# Schematic_v27.net
KiCad netlist of a schematic drawn in EAGLE
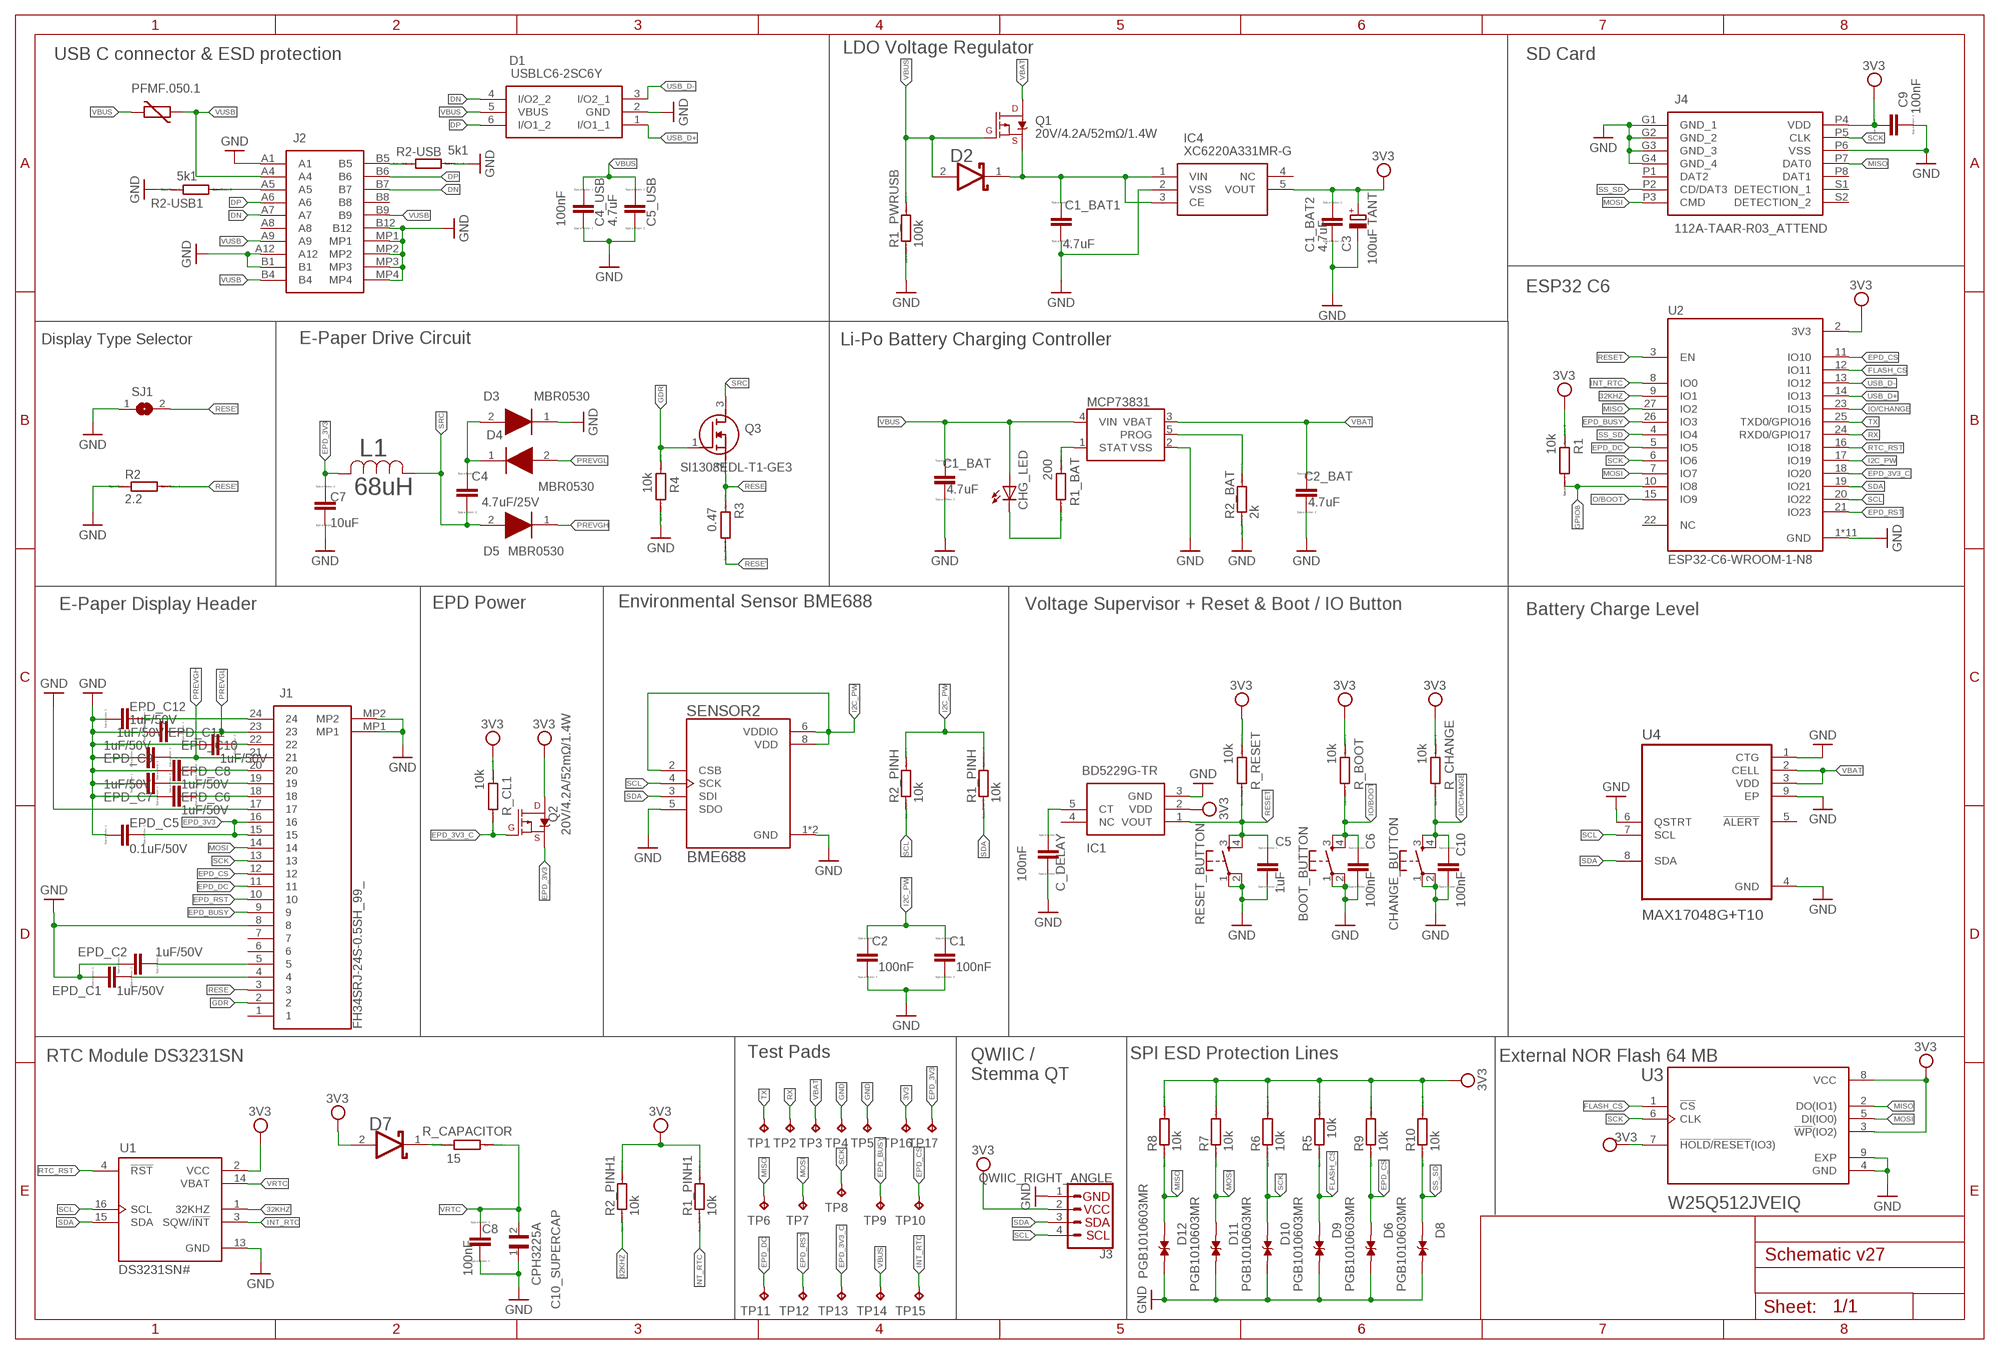
[diagram p0: schematic, sheet 1]

(export (version "E")
  (design (tool "Eeschema 10.0.6"))
  (components
    (comp (ref "BOOT_BUTTON")
      (value "BUTTON_CUSYOMV1")
      (footprint "eagle-import:MYBUTTON")
      (libsource (lib "eagle-import") (part "BUTTON_CUSYOMV1"))
    )
    (comp (ref "C1")
      (value "100nF")
      (footprint "eagle-import:ESP32_WROVER_EAGLE-LTSPICE_C0402")
      (libsource (lib "eagle-import") (part "ESP32_WROVER_EAGLE-LTSPICE_CC0402"))
    )
    (comp (ref "C1_BAT")
      (value "4.7uF")
      (footprint "eagle-import:ESP32_WROVER_EAGLE-LTSPICE_C0402")
      (libsource (lib "eagle-import") (part "ESP32_WROVER_EAGLE-LTSPICE_CC0402"))
    )
    (comp (ref "C1_BAT1")
      (value "4.7uF")
      (footprint "eagle-import:ESP32_WROVER_EAGLE-LTSPICE_C0402")
      (libsource (lib "eagle-import") (part "ESP32_WROVER_EAGLE-LTSPICE_CC0402"))
    )
    (comp (ref "C1_BAT2")
      (value "4.7uF")
      (footprint "eagle-import:ESP32_WROVER_EAGLE-LTSPICE_C0402")
      (libsource (lib "eagle-import") (part "ESP32_WROVER_EAGLE-LTSPICE_CC0402"))
    )
    (comp (ref "C2")
      (value "100nF")
      (footprint "eagle-import:ESP32_WROVER_EAGLE-LTSPICE_C0402")
      (libsource (lib "eagle-import") (part "ESP32_WROVER_EAGLE-LTSPICE_CC0402"))
    )
    (comp (ref "C2_BAT")
      (value "4.7uF")
      (footprint "eagle-import:ESP32_WROVER_EAGLE-LTSPICE_C0402")
      (libsource (lib "eagle-import") (part "ESP32_WROVER_EAGLE-LTSPICE_CC0402"))
    )
    (comp (ref "C3")
      (value "100uF TANT")
      (footprint "eagle-import:RCL_CT3528")
      (libsource (lib "eagle-import") (part "RCL_CPOL-EUCT3528"))
    )
    (comp (ref "C4")
      (value "4.7uF/25V")
      (footprint "eagle-import:ESP32_WROVER_EAGLE-LTSPICE_C0402")
      (libsource (lib "eagle-import") (part "ESP32_WROVER_EAGLE-LTSPICE_CC0402"))
    )
    (comp (ref "C4_USB")
      (value "100nF")
      (footprint "eagle-import:ESP32_WROVER_EAGLE-LTSPICE_C0402")
      (libsource (lib "eagle-import") (part "ESP32_WROVER_EAGLE-LTSPICE_CC0402"))
    )
    (comp (ref "C5")
      (value "1uF")
      (footprint "eagle-import:ESP32_WROVER_EAGLE-LTSPICE_C0402")
      (libsource (lib "eagle-import") (part "ESP32_WROVER_EAGLE-LTSPICE_CC0402"))
    )
    (comp (ref "C5_USB")
      (value "4.7uF")
      (footprint "eagle-import:ESP32_WROVER_EAGLE-LTSPICE_C0402")
      (libsource (lib "eagle-import") (part "ESP32_WROVER_EAGLE-LTSPICE_CC0402"))
    )
    (comp (ref "C6")
      (value "100nF")
      (footprint "eagle-import:ESP32_WROVER_EAGLE-LTSPICE_C0402")
      (libsource (lib "eagle-import") (part "ESP32_WROVER_EAGLE-LTSPICE_CC0402"))
    )
    (comp (ref "C7")
      (value "10uF")
      (footprint "eagle-import:ESP32_WROVER_EAGLE-LTSPICE_C0402")
      (libsource (lib "eagle-import") (part "ESP32_WROVER_EAGLE-LTSPICE_CC0402"))
    )
    (comp (ref "C8")
      (value "100nF")
      (footprint "eagle-import:ESP32_WROVER_EAGLE-LTSPICE_C0402")
      (libsource (lib "eagle-import") (part "ESP32_WROVER_EAGLE-LTSPICE_CC0402"))
    )
    (comp (ref "C9")
      (value "100nF")
      (footprint "eagle-import:ESP32_WROVER_EAGLE-LTSPICE_C0402")
      (libsource (lib "eagle-import") (part "ESP32_WROVER_EAGLE-LTSPICE_CC0402"))
    )
    (comp (ref "C10")
      (value "100nF")
      (footprint "eagle-import:ESP32_WROVER_EAGLE-LTSPICE_C0402")
      (libsource (lib "eagle-import") (part "ESP32_WROVER_EAGLE-LTSPICE_CC0402"))
    )
    (comp (ref "C10_SUPERCAP")
      (value "CPH3225A")
      (footprint "eagle-import:CAPCP3225X100N")
      (fields (field (name "MF") "Seiko Instruments"))
      (libsource (lib "eagle-import") (part "CPH3225A"))
    )
    (comp (ref "CHANGE_BUTTON")
      (value "BUTTON_CUSYOMV1")
      (footprint "eagle-import:MYBUTTON")
      (libsource (lib "eagle-import") (part "BUTTON_CUSYOMV1"))
    )
    (comp (ref "CHG_LED")
      (value "ADAFRUIT_LEDCHIP-LED0603")
      (footprint "eagle-import:ADAFRUIT_CHIP-LED0603")
      (libsource (lib "eagle-import") (part "ADAFRUIT_LEDCHIP-LED0603"))
    )
    (comp (ref "C_DELAY")
      (value "100nF")
      (footprint "eagle-import:ESP32_WROVER_EAGLE-LTSPICE_C0402")
      (libsource (lib "eagle-import") (part "ESP32_WROVER_EAGLE-LTSPICE_CC0402"))
    )
    (comp (ref "D1")
      (value "USBLC6-2SC6Y")
      (footprint "eagle-import:SOT95P280X145-6N")
      (fields (field (name "MF") "STMicroelectronics"))
      (libsource (lib "eagle-import") (part "USBLC6-2SC6Y"))
    )
    (comp (ref "D2")
      (value "ESP32_WROVER_AVX---SD0805S020S1R0_AVX_SD0805S020S1R0_0_0AVX_SD0805S020S1R0_0_0")
      (footprint "eagle-import:ESP32_WROVER_AVX---SD0805S020S1R0_AVX_SD0805S020S1R0_0")
      (fields
        (field (name "DIGIKEY_PART_NUMBER") "478-7800-1-ND")
        (field (name "MF") "AVX")
        (field (name "MOUSER_PART_NUMBER") "581-SD0805S020S1R0")
      )
      (libsource (lib "eagle-import") (part "ESP32_WROVER_AVX---SD0805S020S1R0_AVX_SD0805S020S1R0_0_0AVX_SD0805S020S1R0_0_0"))
    )
    (comp (ref "D3")
      (value "MBR0530")
      (footprint "eagle-import:SOD3716X135N")
      (fields (field (name "MF") "ON Semiconductor"))
      (libsource (lib "eagle-import") (part "MBR0530"))
    )
    (comp (ref "D4")
      (value "MBR0530")
      (footprint "eagle-import:SOD3716X135N")
      (fields (field (name "MF") "ON Semiconductor"))
      (libsource (lib "eagle-import") (part "MBR0530"))
    )
    (comp (ref "D5")
      (value "MBR0530")
      (footprint "eagle-import:SOD3716X135N")
      (fields (field (name "MF") "ON Semiconductor"))
      (libsource (lib "eagle-import") (part "MBR0530"))
    )
    (comp (ref "D6")
      (value "PGB1010603MR")
      (footprint "eagle-import:DIOC1608X36N")
      (fields (field (name "MF") "Littelfuse Inc."))
      (libsource (lib "eagle-import") (part "PGB1010603MR"))
    )
    (comp (ref "D7")
      (value "ESP32_WROVER_AVX---SD0805S020S1R0_AVX_SD0805S020S1R0_0_0AVX_SD0805S020S1R0_0_0")
      (footprint "eagle-import:ESP32_WROVER_AVX---SD0805S020S1R0_AVX_SD0805S020S1R0_0")
      (fields
        (field (name "DIGIKEY_PART_NUMBER") "478-7800-1-ND")
        (field (name "MF") "AVX")
        (field (name "MOUSER_PART_NUMBER") "581-SD0805S020S1R0")
      )
      (libsource (lib "eagle-import") (part "ESP32_WROVER_AVX---SD0805S020S1R0_AVX_SD0805S020S1R0_0_0AVX_SD0805S020S1R0_0_0"))
    )
    (comp (ref "D8")
      (value "PGB1010603MR")
      (footprint "eagle-import:DIOC1608X36N")
      (fields (field (name "MF") "Littelfuse Inc."))
      (libsource (lib "eagle-import") (part "PGB1010603MR"))
    )
    (comp (ref "D9")
      (value "PGB1010603MR")
      (footprint "eagle-import:DIOC1608X36N")
      (fields (field (name "MF") "Littelfuse Inc."))
      (libsource (lib "eagle-import") (part "PGB1010603MR"))
    )
    (comp (ref "D10")
      (value "PGB1010603MR")
      (footprint "eagle-import:DIOC1608X36N")
      (fields (field (name "MF") "Littelfuse Inc."))
      (libsource (lib "eagle-import") (part "PGB1010603MR"))
    )
    (comp (ref "D11")
      (value "PGB1010603MR")
      (footprint "eagle-import:DIOC1608X36N")
      (fields (field (name "MF") "Littelfuse Inc."))
      (libsource (lib "eagle-import") (part "PGB1010603MR"))
    )
    (comp (ref "D12")
      (value "PGB1010603MR")
      (footprint "eagle-import:DIOC1608X36N")
      (fields (field (name "MF") "Littelfuse Inc."))
      (libsource (lib "eagle-import") (part "PGB1010603MR"))
    )
    (comp (ref "EPD_C1")
      (value "1uF/50V")
      (footprint "eagle-import:ESP32_WROVER_EAGLE-LTSPICE_C0402")
      (libsource (lib "eagle-import") (part "ESP32_WROVER_EAGLE-LTSPICE_CC0402"))
    )
    (comp (ref "EPD_C2")
      (value "1uF/50V")
      (footprint "eagle-import:ESP32_WROVER_EAGLE-LTSPICE_C0402")
      (libsource (lib "eagle-import") (part "ESP32_WROVER_EAGLE-LTSPICE_CC0402"))
    )
    (comp (ref "EPD_C5")
      (value "0.1uF/50V")
      (footprint "eagle-import:ESP32_WROVER_EAGLE-LTSPICE_C0402")
      (libsource (lib "eagle-import") (part "ESP32_WROVER_EAGLE-LTSPICE_CC0402"))
    )
    (comp (ref "EPD_C6")
      (value "1uF/50V")
      (footprint "eagle-import:ESP32_WROVER_EAGLE-LTSPICE_C0402")
      (libsource (lib "eagle-import") (part "ESP32_WROVER_EAGLE-LTSPICE_CC0402"))
    )
    (comp (ref "EPD_C7")
      (value "1uF/50V")
      (footprint "eagle-import:ESP32_WROVER_EAGLE-LTSPICE_C0402")
      (libsource (lib "eagle-import") (part "ESP32_WROVER_EAGLE-LTSPICE_CC0402"))
    )
    (comp (ref "EPD_C8")
      (value "1uF/50V")
      (footprint "eagle-import:ESP32_WROVER_EAGLE-LTSPICE_C0402")
      (libsource (lib "eagle-import") (part "ESP32_WROVER_EAGLE-LTSPICE_CC0402"))
    )
    (comp (ref "EPD_C9")
      (value "1uF/50V")
      (footprint "eagle-import:ESP32_WROVER_EAGLE-LTSPICE_C0402")
      (libsource (lib "eagle-import") (part "ESP32_WROVER_EAGLE-LTSPICE_CC0402"))
    )
    (comp (ref "EPD_C10")
      (value "1uF/50V")
      (footprint "eagle-import:ESP32_WROVER_EAGLE-LTSPICE_C0402")
      (libsource (lib "eagle-import") (part "ESP32_WROVER_EAGLE-LTSPICE_CC0402"))
    )
    (comp (ref "EPD_C11")
      (value "1uF/50V")
      (footprint "eagle-import:ESP32_WROVER_EAGLE-LTSPICE_C0402")
      (libsource (lib "eagle-import") (part "ESP32_WROVER_EAGLE-LTSPICE_CC0402"))
    )
    (comp (ref "EPD_C12")
      (value "1uF/50V")
      (footprint "eagle-import:ESP32_WROVER_EAGLE-LTSPICE_C0402")
      (libsource (lib "eagle-import") (part "ESP32_WROVER_EAGLE-LTSPICE_CC0402"))
    )
    (comp (ref "IC1")
      (value "BD5229G-TR")
      (footprint "eagle-import:SOT95P280X125-5N")
      (fields (field (name "MOUSER_PART_NUMBER") "755-BD5229G-TR"))
      (libsource (lib "eagle-import") (part "BD5229G-TR"))
    )
    (comp (ref "IC4")
      (value "XC6220A331MR-G")
      (footprint "eagle-import:SOT95P280X120-5N")
      (fields (field (name "MOUSER_PART_NUMBER") "865-XC6220A331MR-G"))
      (libsource (lib "eagle-import") (part "XC6220A331MR-G"))
    )
    (comp (ref "J1")
      (value "FH34SRJ-24S-0.5SH_99_")
      (footprint "eagle-import:FH34SRJ24S05SH99")
      (fields
        (field (name "MANUFACTURER_PART_NUMBER") "FH34SRJ-24S-0.5SH(99)")
        (field (name "MOUSER_PART_NUMBER") "798-FH34SRJ24S05SH99")
      )
      (libsource (lib "eagle-import") (part "FH34SRJ-24S-0.5SH_99_"))
    )
    (comp (ref "J2")
      (value "SAMACSYS_PARTS_USB4110-GF-A")
      (footprint "eagle-import:SAMACSYS_PARTS_USB4110GFA")
      (fields
        (field (name "MANUFACTURER_PART_NUMBER") "USB4110-GF-A")
        (field (name "MOUSER_PART_NUMBER") "640-USB4110-GF-A")
      )
      (libsource (lib "eagle-import") (part "SAMACSYS_PARTS_USB4110-GF-A"))
    )
    (comp (ref "J3")
      (value "QWIIC_RIGHT_ANGLE")
      (footprint "eagle-import:JST04_1MM_RA")
      (libsource (lib "eagle-import") (part "QWIIC_CONNECTORJS-1MM"))
    )
    (comp (ref "J4")
      (value "112A-TAAR-R03_ATTEND")
      (footprint "eagle-import:112ATAARR03ATTEND")
      (fields (field (name "MANUFACTURER_PART_NUMBER") "112A-TAAR-R03 ATTEND"))
      (libsource (lib "eagle-import") (part "112A-TAAR-R03_ATTEND"))
    )
    (comp (ref "L1")
      (value "68uH")
      (footprint "eagle-import:IND_4828-WE-TPC_WRE")
      (fields
        (field (name "MANUFACTURER_PART_NUMBER") "744043680")
        (field (name "COPYRIGHT") "Copyright (C) 2024 Ultra Librarian. All rights reserved.")
      )
      (libsource (lib "eagle-import") (part "744043680IND_4828-WE-TPC_WRE"))
    )
    (comp (ref "MCP73831")
      (value "ESP32_WROVER_SPARKFUN-IC-POWER_MCP73831")
      (footprint "eagle-import:ESP32_WROVER_SPARKFUN-IC-POWER_SOT23-5")
      (libsource (lib "eagle-import") (part "ESP32_WROVER_SPARKFUN-IC-POWER_MCP73831"))
    )
    (comp (ref "PFMF.050.1")
      (value "ESP32C6_VARISTORCN1812")
      (footprint "eagle-import:ESP32C6_VARISTOR_CT_CN1812")
      (libsource (lib "eagle-import") (part "ESP32C6_VARISTORCN1812"))
    )
    (comp (ref "Q1")
      (value "20V/4.2A/52mΩ/1.4W")
      (footprint "eagle-import:ESP32_WROVER_SPARKFUN-DISCRETESEMI_SOT23-3")
      (libsource (lib "eagle-import") (part "ESP32_WROVER_SPARKFUN-DISCRETESEMI_MOSFET_PCH-DMG2305UX-7"))
    )
    (comp (ref "Q2")
      (value "20V/4.2A/52mΩ/1.4W")
      (footprint "eagle-import:ESP32_WROVER_SPARKFUN-DISCRETESEMI_SOT23-3")
      (libsource (lib "eagle-import") (part "ESP32_WROVER_SPARKFUN-DISCRETESEMI_MOSFET_PCH-DMG2305UX-7"))
    )
    (comp (ref "Q3")
      (value "SI1308EDL-T1-GE3")
      (footprint "eagle-import:SOT65P210X110-3N")
      (fields (field (name "MF") "Vishay Siliconix"))
      (libsource (lib "eagle-import") (part "SI1308EDL-T1-GE3"))
    )
    (comp (ref "R1")
      (value "10k")
      (footprint "eagle-import:ESP32_WROVER_EAGLE-LTSPICE_R0402")
      (libsource (lib "eagle-import") (part "ESP32_WROVER_EAGLE-LTSPICE_RR0402"))
    )
    (comp (ref "R1_BAT")
      (value "200")
      (footprint "eagle-import:ESP32_WROVER_EAGLE-LTSPICE_R0402")
      (libsource (lib "eagle-import") (part "ESP32_WROVER_EAGLE-LTSPICE_RR0402"))
    )
    (comp (ref "R1_PINH")
      (value "10k")
      (footprint "eagle-import:ESP32_WROVER_EAGLE-LTSPICE_R0402")
      (libsource (lib "eagle-import") (part "ESP32_WROVER_EAGLE-LTSPICE_RR0402"))
    )
    (comp (ref "R1_PINH1")
      (value "10k")
      (footprint "eagle-import:ESP32_WROVER_EAGLE-LTSPICE_R0402")
      (libsource (lib "eagle-import") (part "ESP32_WROVER_EAGLE-LTSPICE_RR0402"))
    )
    (comp (ref "R1_PWRUSB")
      (value "100k")
      (footprint "eagle-import:ESP32_WROVER_EAGLE-LTSPICE_R0402")
      (libsource (lib "eagle-import") (part "ESP32_WROVER_EAGLE-LTSPICE_RR0402"))
    )
    (comp (ref "R2")
      (value "2.2")
      (footprint "eagle-import:ESP32_WROVER_EAGLE-LTSPICE_R0402")
      (libsource (lib "eagle-import") (part "ESP32_WROVER_EAGLE-LTSPICE_RR0402"))
    )
    (comp (ref "R2-USB")
      (value "5k1")
      (footprint "eagle-import:ESP32_WROVER_EAGLE-LTSPICE_R0402")
      (libsource (lib "eagle-import") (part "ESP32_WROVER_EAGLE-LTSPICE_RR0402"))
    )
    (comp (ref "R2-USB1")
      (value "5k1")
      (footprint "eagle-import:ESP32_WROVER_EAGLE-LTSPICE_R0402")
      (libsource (lib "eagle-import") (part "ESP32_WROVER_EAGLE-LTSPICE_RR0402"))
    )
    (comp (ref "R2_BAT")
      (value "2k")
      (footprint "eagle-import:ESP32_WROVER_EAGLE-LTSPICE_R0402")
      (libsource (lib "eagle-import") (part "ESP32_WROVER_EAGLE-LTSPICE_RR0402"))
    )
    (comp (ref "R2_PINH")
      (value "10k")
      (footprint "eagle-import:ESP32_WROVER_EAGLE-LTSPICE_R0402")
      (libsource (lib "eagle-import") (part "ESP32_WROVER_EAGLE-LTSPICE_RR0402"))
    )
    (comp (ref "R2_PINH1")
      (value "10k")
      (footprint "eagle-import:ESP32_WROVER_EAGLE-LTSPICE_R0402")
      (libsource (lib "eagle-import") (part "ESP32_WROVER_EAGLE-LTSPICE_RR0402"))
    )
    (comp (ref "R3")
      (value "0.47")
      (footprint "eagle-import:ESP32_WROVER_EAGLE-LTSPICE_R0402")
      (libsource (lib "eagle-import") (part "ESP32_WROVER_EAGLE-LTSPICE_RR0402"))
    )
    (comp (ref "R4")
      (value "10k")
      (footprint "eagle-import:ESP32_WROVER_EAGLE-LTSPICE_R0402")
      (libsource (lib "eagle-import") (part "ESP32_WROVER_EAGLE-LTSPICE_RR0402"))
    )
    (comp (ref "R5")
      (value "10k")
      (footprint "eagle-import:ESP32_WROVER_EAGLE-LTSPICE_R0402")
      (libsource (lib "eagle-import") (part "ESP32_WROVER_EAGLE-LTSPICE_RR0402"))
    )
    (comp (ref "R6")
      (value "10k")
      (footprint "eagle-import:ESP32_WROVER_EAGLE-LTSPICE_R0402")
      (libsource (lib "eagle-import") (part "ESP32_WROVER_EAGLE-LTSPICE_RR0402"))
    )
    (comp (ref "R7")
      (value "10k")
      (footprint "eagle-import:ESP32_WROVER_EAGLE-LTSPICE_R0402")
      (libsource (lib "eagle-import") (part "ESP32_WROVER_EAGLE-LTSPICE_RR0402"))
    )
    (comp (ref "R8")
      (value "10k")
      (footprint "eagle-import:ESP32_WROVER_EAGLE-LTSPICE_R0402")
      (libsource (lib "eagle-import") (part "ESP32_WROVER_EAGLE-LTSPICE_RR0402"))
    )
    (comp (ref "R9")
      (value "10k")
      (footprint "eagle-import:ESP32_WROVER_EAGLE-LTSPICE_R0402")
      (libsource (lib "eagle-import") (part "ESP32_WROVER_EAGLE-LTSPICE_RR0402"))
    )
    (comp (ref "R10")
      (value "10k")
      (footprint "eagle-import:ESP32_WROVER_EAGLE-LTSPICE_R0402")
      (libsource (lib "eagle-import") (part "ESP32_WROVER_EAGLE-LTSPICE_RR0402"))
    )
    (comp (ref "RESET_BUTTON")
      (value "BUTTON_CUSYOMV1")
      (footprint "eagle-import:MYBUTTON")
      (libsource (lib "eagle-import") (part "BUTTON_CUSYOMV1"))
    )
    (comp (ref "R_BOOT")
      (value "10k")
      (footprint "eagle-import:ESP32_WROVER_EAGLE-LTSPICE_R0402")
      (libsource (lib "eagle-import") (part "ESP32_WROVER_EAGLE-LTSPICE_RR0402"))
    )
    (comp (ref "R_CAPACITOR")
      (value "15")
      (footprint "eagle-import:ESP32_WROVER_EAGLE-LTSPICE_R0402")
      (libsource (lib "eagle-import") (part "ESP32_WROVER_EAGLE-LTSPICE_RR0402"))
    )
    (comp (ref "R_CHANGE")
      (value "10k")
      (footprint "eagle-import:ESP32_WROVER_EAGLE-LTSPICE_R0402")
      (libsource (lib "eagle-import") (part "ESP32_WROVER_EAGLE-LTSPICE_RR0402"))
    )
    (comp (ref "R_CL1")
      (value "10k")
      (footprint "eagle-import:ESP32_WROVER_EAGLE-LTSPICE_R0402")
      (libsource (lib "eagle-import") (part "ESP32_WROVER_EAGLE-LTSPICE_RR0402"))
    )
    (comp (ref "R_RESET")
      (value "10k")
      (footprint "eagle-import:ESP32_WROVER_EAGLE-LTSPICE_R0402")
      (libsource (lib "eagle-import") (part "ESP32_WROVER_EAGLE-LTSPICE_RR0402"))
    )
    (comp (ref "SENSOR2")
      (value "BME688")
      (footprint "eagle-import:ESP32_WROVER_BME680_PSON80P300X300X100-8N")
      (fields (field (name "MF") "Bosch Sensortec") (field (name "MP") "BME680"))
      (libsource (lib "eagle-import") (part "ESP32_WROVER_BME680_BME680"))
    )
    (comp (ref "SJ1") (value "SJ") (footprint "eagle-import:SJ") (libsource (lib "eagle-import") (part "SJ")))
    (comp (ref "TP1")
      (value "TPTP20R")
      (footprint "eagle-import:TP20R")
      (libsource (lib "eagle-import") (part "TPTP20R"))
    )
    (comp (ref "TP2")
      (value "TPTP20R")
      (footprint "eagle-import:TP20R")
      (libsource (lib "eagle-import") (part "TPTP20R"))
    )
    (comp (ref "TP3")
      (value "TPTP20R")
      (footprint "eagle-import:TP20R")
      (libsource (lib "eagle-import") (part "TPTP20R"))
    )
    (comp (ref "TP4")
      (value "TPTP20R")
      (footprint "eagle-import:TP20R")
      (libsource (lib "eagle-import") (part "TPTP20R"))
    )
    (comp (ref "TP5")
      (value "TPTP20R")
      (footprint "eagle-import:TP20R")
      (libsource (lib "eagle-import") (part "TPTP20R"))
    )
    (comp (ref "TP6")
      (value "TPTP20R")
      (footprint "eagle-import:TP20R")
      (libsource (lib "eagle-import") (part "TPTP20R"))
    )
    (comp (ref "TP7")
      (value "TPTP20R")
      (footprint "eagle-import:TP20R")
      (libsource (lib "eagle-import") (part "TPTP20R"))
    )
    (comp (ref "TP8")
      (value "TPTP20R")
      (footprint "eagle-import:TP20R")
      (libsource (lib "eagle-import") (part "TPTP20R"))
    )
    (comp (ref "TP9")
      (value "TPTP20R")
      (footprint "eagle-import:TP20R")
      (libsource (lib "eagle-import") (part "TPTP20R"))
    )
    (comp (ref "TP10")
      (value "TPTP20R")
      (footprint "eagle-import:TP20R")
      (libsource (lib "eagle-import") (part "TPTP20R"))
    )
    (comp (ref "TP11")
      (value "TPTP20R")
      (footprint "eagle-import:TP20R")
      (libsource (lib "eagle-import") (part "TPTP20R"))
    )
    (comp (ref "TP12")
      (value "TPTP20R")
      (footprint "eagle-import:TP20R")
      (libsource (lib "eagle-import") (part "TPTP20R"))
    )
    (comp (ref "TP13")
      (value "TPTP20R")
      (footprint "eagle-import:TP20R")
      (libsource (lib "eagle-import") (part "TPTP20R"))
    )
    (comp (ref "TP14")
      (value "TPTP20R")
      (footprint "eagle-import:TP20R")
      (libsource (lib "eagle-import") (part "TPTP20R"))
    )
    (comp (ref "TP15")
      (value "TPTP20R")
      (footprint "eagle-import:TP20R")
      (libsource (lib "eagle-import") (part "TPTP20R"))
    )
    (comp (ref "TP16")
      (value "TPTP20R")
      (footprint "eagle-import:TP20R")
      (libsource (lib "eagle-import") (part "TPTP20R"))
    )
    (comp (ref "TP17")
      (value "TPTP20R")
      (footprint "eagle-import:TP20R")
      (libsource (lib "eagle-import") (part "TPTP20R"))
    )
    (comp (ref "U1")
      (value "DS3231SN#")
      (footprint "eagle-import:SOIC127P1032X265-16N")
      (fields (field (name "MF") "Analog Devices"))
      (libsource (lib "eagle-import") (part "DS3231SN#"))
    )
    (comp (ref "U2")
      (value "ESP32-C6-WROOM-1-N8")
      (footprint "eagle-import:XCVR_ESP32-C6-WROOM-1-N8")
      (fields (field (name "MF") "Espressif Systems"))
      (libsource (lib "eagle-import") (part "ESP32-C6-WROOM-1-N8"))
    )
    (comp (ref "U3")
      (value "W25Q512JVEIQ")
      (footprint "eagle-import:SON127P600X800X80-9N")
      (fields (field (name "MF") "Winbond Electronics"))
      (libsource (lib "eagle-import") (part "W25Q512JVEIQ"))
    )
    (comp (ref "U4")
      (value "MAX17048G+T10")
      (footprint "eagle-import:SON50P200X200X80-9N")
      (fields (field (name "MF") "Analog Devices"))
      (libsource (lib "eagle-import") (part "MAX17048G+T10"))
    )
  )
  (nets
    (net (code "1") (name "3V3") (class "Default")
      (node (ref "C1_BAT2") (pin "1") (pinfunction "1_1") (pintype "passive"))
      (node (ref "C3") (pin "+") (pinfunction "+_+") (pintype "passive"))
      (node (ref "C9") (pin "1") (pinfunction "1_1") (pintype "passive"))
      (node (ref "D7") (pin "2") (pinfunction "ANODE_2") (pintype "bidirectional"))
      (node (ref "IC1") (pin "2") (pinfunction "VDD_2") (pintype "bidirectional"))
      (node (ref "IC4") (pin "5") (pinfunction "VOUT_5") (pintype "bidirectional"))
      (node (ref "J3") (pin "2") (pinfunction "2_2") (pintype "power_in"))
      (node (ref "J4") (pin "P4") (pinfunction "VDD_P4") (pintype "bidirectional"))
      (node (ref "Q2") (pin "3") (pinfunction "D_3") (pintype "bidirectional"))
      (node (ref "R1") (pin "2") (pinfunction "2_2") (pintype "passive"))
      (node (ref "R10") (pin "2") (pinfunction "2_2") (pintype "passive"))
      (node (ref "R1_PINH1") (pin "2") (pinfunction "2_2") (pintype "passive"))
      (node (ref "R2_PINH1") (pin "2") (pinfunction "2_2") (pintype "passive"))
      (node (ref "R5") (pin "2") (pinfunction "2_2") (pintype "passive"))
      (node (ref "R6") (pin "2") (pinfunction "2_2") (pintype "passive"))
      (node (ref "R7") (pin "2") (pinfunction "2_2") (pintype "passive"))
      (node (ref "R8") (pin "2") (pinfunction "2_2") (pintype "passive"))
      (node (ref "R9") (pin "2") (pinfunction "2_2") (pintype "passive"))
      (node (ref "R_BOOT") (pin "2") (pinfunction "2_2") (pintype "passive"))
      (node (ref "R_CHANGE") (pin "2") (pinfunction "2_2") (pintype "passive"))
      (node (ref "R_CL1") (pin "2") (pinfunction "2_2") (pintype "passive"))
      (node (ref "R_RESET") (pin "2") (pinfunction "2_2") (pintype "passive"))
      (node (ref "TP16") (pin "TP") (pinfunction "TP_TP") (pintype "input"))
      (node (ref "U1") (pin "2") (pinfunction "VCC_2") (pintype "power_in"))
      (node (ref "U2") (pin "2") (pinfunction "3V3_2") (pintype "power_in"))
      (node (ref "U3") (pin "3") (pinfunction "~{WP}(IO2)_3") (pintype "bidirectional"))
      (node (ref "U3") (pin "7") (pinfunction "~{HOLD}/~{RESET}(IO3)_7") (pintype "bidirectional"))
      (node (ref "U3") (pin "8") (pinfunction "VCC_8") (pintype "power_in"))
    )
    (net (code "2") (name "32KHZ") (class "Default")
      (node (ref "R2_PINH1") (pin "1") (pinfunction "1_1") (pintype "passive"))
      (node (ref "U1") (pin "1") (pinfunction "32KHZ_1") (pintype "output"))
      (node (ref "U2") (pin "9") (pinfunction "IO1_9") (pintype "bidirectional"))
    )
    (net (code "3") (name "DN") (class "Default")
      (node (ref "D1") (pin "4") (pinfunction "I/O2_2_4") (pintype "bidirectional"))
      (node (ref "J2") (pin "A7") (pinfunction "A7_A7") (pintype "bidirectional"))
      (node (ref "J2") (pin "B7") (pinfunction "B7_B7") (pintype "bidirectional"))
    )
    (net (code "4") (name "DP") (class "Default")
      (node (ref "D1") (pin "6") (pinfunction "I/O1_2_6") (pintype "bidirectional"))
      (node (ref "J2") (pin "A6") (pinfunction "A6_A6") (pintype "bidirectional"))
      (node (ref "J2") (pin "B6") (pinfunction "B6_B6") (pintype "bidirectional"))
    )
    (net (code "5") (name "EPD_3V3") (class "Default")
      (node (ref "C7") (pin "2") (pinfunction "2_2") (pintype "passive"))
      (node (ref "EPD_C5") (pin "2") (pinfunction "2_2") (pintype "passive"))
      (node (ref "J1") (pin "15") (pinfunction "15_15") (pintype "bidirectional"))
      (node (ref "J1") (pin "16") (pinfunction "16_16") (pintype "bidirectional"))
      (node (ref "L1") (pin "2") (pinfunction "2_2") (pintype "passive"))
      (node (ref "Q2") (pin "2") (pinfunction "S_2") (pintype "bidirectional"))
      (node (ref "TP17") (pin "TP") (pinfunction "TP_TP") (pintype "input"))
    )
    (net (code "6") (name "EPD_3V3_C") (class "Default")
      (node (ref "Q2") (pin "1") (pinfunction "G_1") (pintype "bidirectional"))
      (node (ref "R_CL1") (pin "1") (pinfunction "1_1") (pintype "passive"))
      (node (ref "TP13") (pin "TP") (pinfunction "TP_TP") (pintype "input"))
      (node (ref "U2") (pin "18") (pinfunction "IO20_18") (pintype "bidirectional"))
    )
    (net (code "7") (name "EPD_BUSY") (class "Default")
      (node (ref "J1") (pin "9") (pinfunction "9_9") (pintype "bidirectional"))
      (node (ref "TP9") (pin "TP") (pinfunction "TP_TP") (pintype "input"))
      (node (ref "U2") (pin "26") (pinfunction "IO3_26") (pintype "bidirectional"))
    )
    (net (code "8") (name "EPD_CS") (class "Default")
      (node (ref "D6") (pin "1") (pinfunction "1_1") (pintype "passive"))
      (node (ref "J1") (pin "12") (pinfunction "12_12") (pintype "bidirectional"))
      (node (ref "R9") (pin "1") (pinfunction "1_1") (pintype "passive"))
      (node (ref "TP10") (pin "TP") (pinfunction "TP_TP") (pintype "input"))
      (node (ref "U2") (pin "11") (pinfunction "IO10_11") (pintype "bidirectional"))
    )
    (net (code "9") (name "EPD_DC") (class "Default")
      (node (ref "J1") (pin "11") (pinfunction "11_11") (pintype "bidirectional"))
      (node (ref "TP11") (pin "TP") (pinfunction "TP_TP") (pintype "input"))
      (node (ref "U2") (pin "5") (pinfunction "IO5_5") (pintype "bidirectional"))
    )
    (net (code "10") (name "EPD_RST") (class "Default")
      (node (ref "J1") (pin "10") (pinfunction "10_10") (pintype "bidirectional"))
      (node (ref "TP12") (pin "TP") (pinfunction "TP_TP") (pintype "input"))
      (node (ref "U2") (pin "21") (pinfunction "IO23_21") (pintype "bidirectional"))
    )
    (net (code "11") (name "FLASH_CS") (class "Default")
      (node (ref "D9") (pin "1") (pinfunction "1_1") (pintype "passive"))
      (node (ref "R5") (pin "1") (pinfunction "1_1") (pintype "passive"))
      (node (ref "U2") (pin "12") (pinfunction "IO11_12") (pintype "bidirectional"))
      (node (ref "U3") (pin "1") (pinfunction "~{CS}_1") (pintype "input"))
    )
    (net (code "12") (name "GDR") (class "Default")
      (node (ref "J1") (pin "2") (pinfunction "2_2") (pintype "bidirectional"))
      (node (ref "Q3") (pin "1") (pinfunction "G_1") (pintype "bidirectional"))
      (node (ref "R4") (pin "2") (pinfunction "2_2") (pintype "passive"))
    )
    (net (code "13") (name "GND") (class "Default")
      (node (ref "BOOT_BUTTON") (pin "1") (pinfunction "1_1") (pintype "passive"))
      (node (ref "BOOT_BUTTON") (pin "2") (pinfunction "2_2") (pintype "passive"))
      (node (ref "C1") (pin "2") (pinfunction "2_2") (pintype "passive"))
      (node (ref "C10") (pin "2") (pinfunction "2_2") (pintype "passive"))
      (node (ref "C10_SUPERCAP") (pin "1") (pinfunction "1_1") (pintype "passive"))
      (node (ref "C1_BAT") (pin "2") (pinfunction "2_2") (pintype "passive"))
      (node (ref "C1_BAT1") (pin "2") (pinfunction "2_2") (pintype "passive"))
      (node (ref "C1_BAT2") (pin "2") (pinfunction "2_2") (pintype "passive"))
      (node (ref "C2") (pin "2") (pinfunction "2_2") (pintype "passive"))
      (node (ref "C2_BAT") (pin "2") (pinfunction "2_2") (pintype "passive"))
      (node (ref "C3") (pin "-") (pinfunction "-_-") (pintype "passive"))
      (node (ref "C4_USB") (pin "2") (pinfunction "2_2") (pintype "passive"))
      (node (ref "C5") (pin "2") (pinfunction "2_2") (pintype "passive"))
      (node (ref "C5_USB") (pin "2") (pinfunction "2_2") (pintype "passive"))
      (node (ref "C6") (pin "2") (pinfunction "2_2") (pintype "passive"))
      (node (ref "C7") (pin "1") (pinfunction "1_1") (pintype "passive"))
      (node (ref "C8") (pin "1") (pinfunction "1_1") (pintype "passive"))
      (node (ref "C9") (pin "2") (pinfunction "2_2") (pintype "passive"))
      (node (ref "CHANGE_BUTTON") (pin "1") (pinfunction "1_1") (pintype "passive"))
      (node (ref "CHANGE_BUTTON") (pin "2") (pinfunction "2_2") (pintype "passive"))
      (node (ref "C_DELAY") (pin "2") (pinfunction "2_2") (pintype "passive"))
      (node (ref "D1") (pin "2") (pinfunction "GND_2") (pintype "bidirectional"))
      (node (ref "D10") (pin "2") (pinfunction "2_2") (pintype "passive"))
      (node (ref "D11") (pin "2") (pinfunction "2_2") (pintype "passive"))
      (node (ref "D12") (pin "2") (pinfunction "2_2") (pintype "passive"))
      (node (ref "D3") (pin "1") (pinfunction "K_1") (pintype "bidirectional"))
      (node (ref "D6") (pin "2") (pinfunction "2_2") (pintype "passive"))
      (node (ref "D8") (pin "2") (pinfunction "2_2") (pintype "passive"))
      (node (ref "D9") (pin "2") (pinfunction "2_2") (pintype "passive"))
      (node (ref "EPD_C1") (pin "1") (pinfunction "1_1") (pintype "passive"))
      (node (ref "EPD_C10") (pin "1") (pinfunction "1_1") (pintype "passive"))
      (node (ref "EPD_C11") (pin "1") (pinfunction "1_1") (pintype "passive"))
      (node (ref "EPD_C12") (pin "1") (pinfunction "1_1") (pintype "passive"))
      (node (ref "EPD_C2") (pin "1") (pinfunction "1_1") (pintype "passive"))
      (node (ref "EPD_C5") (pin "1") (pinfunction "1_1") (pintype "passive"))
      (node (ref "EPD_C6") (pin "1") (pinfunction "1_1") (pintype "passive"))
      (node (ref "EPD_C7") (pin "1") (pinfunction "1_1") (pintype "passive"))
      (node (ref "EPD_C8") (pin "1") (pinfunction "1_1") (pintype "passive"))
      (node (ref "EPD_C9") (pin "1") (pinfunction "1_1") (pintype "passive"))
      (node (ref "IC1") (pin "3") (pinfunction "GND_3") (pintype "bidirectional"))
      (node (ref "IC4") (pin "2") (pinfunction "VSS_2") (pintype "bidirectional"))
      (node (ref "J1") (pin "17") (pinfunction "17_17") (pintype "bidirectional"))
      (node (ref "J1") (pin "8") (pinfunction "8_8") (pintype "bidirectional"))
      (node (ref "J1") (pin "MP1") (pinfunction "MP1_MP1") (pintype "bidirectional"))
      (node (ref "J1") (pin "MP2") (pinfunction "MP2_MP2") (pintype "bidirectional"))
      (node (ref "J2") (pin "A1") (pinfunction "A1_A1") (pintype "bidirectional"))
      (node (ref "J2") (pin "A12") (pinfunction "A12_A12") (pintype "bidirectional"))
      (node (ref "J2") (pin "B1") (pinfunction "B1_B1") (pintype "bidirectional"))
      (node (ref "J2") (pin "B12") (pinfunction "B12_B12") (pintype "bidirectional"))
      (node (ref "J2") (pin "MP1") (pinfunction "MP1_MP1") (pintype "bidirectional"))
      (node (ref "J2") (pin "MP2") (pinfunction "MP2_MP2") (pintype "bidirectional"))
      (node (ref "J2") (pin "MP3") (pinfunction "MP3_MP3") (pintype "bidirectional"))
      (node (ref "J2") (pin "MP4") (pinfunction "MP4_MP4") (pintype "bidirectional"))
      (node (ref "J3") (pin "1") (pinfunction "1_1") (pintype "power_in"))
      (node (ref "J4") (pin "G1") (pinfunction "GND_1_G1") (pintype "bidirectional"))
      (node (ref "J4") (pin "G2") (pinfunction "GND_2_G2") (pintype "bidirectional"))
      (node (ref "J4") (pin "G3") (pinfunction "GND_3_G3") (pintype "bidirectional"))
      (node (ref "J4") (pin "G4") (pinfunction "GND_4_G4") (pintype "bidirectional"))
      (node (ref "J4") (pin "P6") (pinfunction "VSS_P6") (pintype "bidirectional"))
      (node (ref "MCP73831") (pin "2") (pinfunction "VSS_2") (pintype "power_in"))
      (node (ref "R1_PWRUSB") (pin "1") (pinfunction "1_1") (pintype "passive"))
      (node (ref "R2") (pin "1") (pinfunction "1_1") (pintype "passive"))
      (node (ref "R2-USB") (pin "2") (pinfunction "2_2") (pintype "passive"))
      (node (ref "R2-USB1") (pin "1") (pinfunction "1_1") (pintype "passive"))
      (node (ref "R2_BAT") (pin "1") (pinfunction "1_1") (pintype "passive"))
      (node (ref "R4") (pin "1") (pinfunction "1_1") (pintype "passive"))
      (node (ref "RESET_BUTTON") (pin "1") (pinfunction "1_1") (pintype "passive"))
      (node (ref "RESET_BUTTON") (pin "2") (pinfunction "2_2") (pintype "passive"))
      (node (ref "SENSOR2") (pin "1") (pinfunction "GND_1") (pintype "power_in"))
      (node (ref "SENSOR2") (pin "5") (pinfunction "SDO_5") (pintype "bidirectional"))
      (node (ref "SENSOR2") (pin "7") (pinfunction "GND_7") (pintype "power_in"))
      (node (ref "SJ1") (pin "1") (pinfunction "1_1") (pintype "passive"))
      (node (ref "TP4") (pin "TP") (pinfunction "TP_TP") (pintype "input"))
      (node (ref "TP5") (pin "TP") (pinfunction "TP_TP") (pintype "input"))
      (node (ref "U1") (pin "13") (pinfunction "GND_13") (pintype "power_in"))
      (node (ref "U2") (pin "1") (pinfunction "GND_1") (pintype "power_in"))
      (node (ref "U2") (pin "28") (pinfunction "GND_28") (pintype "power_in"))
      (node (ref "U2") (pin "29_1") (pinfunction "GND_29_1") (pintype "power_in"))
      (node (ref "U2") (pin "29_2") (pinfunction "GND_29_2") (pintype "power_in"))
      (node (ref "U2") (pin "29_3") (pinfunction "GND_29_3") (pintype "power_in"))
      (node (ref "U2") (pin "29_4") (pinfunction "GND_29_4") (pintype "power_in"))
      (node (ref "U2") (pin "29_5") (pinfunction "GND_29_5") (pintype "power_in"))
      (node (ref "U2") (pin "29_6") (pinfunction "GND_29_6") (pintype "power_in"))
      (node (ref "U2") (pin "29_7") (pinfunction "GND_29_7") (pintype "power_in"))
      (node (ref "U2") (pin "29_8") (pinfunction "GND_29_8") (pintype "power_in"))
      (node (ref "U2") (pin "29_9") (pinfunction "GND_29_9") (pintype "power_in"))
      (node (ref "U3") (pin "4") (pinfunction "GND_4") (pintype "power_in"))
      (node (ref "U3") (pin "9") (pinfunction "EXP_9") (pintype "passive"))
      (node (ref "U4") (pin "1") (pinfunction "CTG_1") (pintype "power_in"))
      (node (ref "U4") (pin "4") (pinfunction "GND_4") (pintype "power_in"))
      (node (ref "U4") (pin "6") (pinfunction "QSTRT_6") (pintype "input"))
      (node (ref "U4") (pin "9") (pinfunction "EP_9") (pintype "power_in"))
    )
    (net (code "14") (name "GPIO8") (class "Default")
      (node (ref "R1") (pin "1") (pinfunction "1_1") (pintype "passive"))
      (node (ref "U2") (pin "10") (pinfunction "IO8_10") (pintype "bidirectional"))
    )
    (net (code "15") (name "I2C_PW") (class "Default")
      (node (ref "C1") (pin "1") (pinfunction "1_1") (pintype "passive"))
      (node (ref "C2") (pin "1") (pinfunction "1_1") (pintype "passive"))
      (node (ref "R1_PINH") (pin "2") (pinfunction "2_2") (pintype "passive"))
      (node (ref "R2_PINH") (pin "2") (pinfunction "2_2") (pintype "passive"))
      (node (ref "SENSOR2") (pin "2") (pinfunction "CSB_2") (pintype "input"))
      (node (ref "SENSOR2") (pin "6") (pinfunction "VDDIO_6") (pintype "power_in"))
      (node (ref "SENSOR2") (pin "8") (pinfunction "VDD_8") (pintype "power_in"))
      (node (ref "U2") (pin "17") (pinfunction "IO19_17") (pintype "bidirectional"))
    )
    (net (code "16") (name "INT_RTC") (class "Default")
      (node (ref "R1_PINH1") (pin "1") (pinfunction "1_1") (pintype "passive"))
      (node (ref "TP15") (pin "TP") (pinfunction "TP_TP") (pintype "input"))
      (node (ref "U1") (pin "3") (pinfunction "SQW/~{INT}_3") (pintype "output"))
      (node (ref "U2") (pin "8") (pinfunction "IO0_8") (pintype "bidirectional"))
    )
    (net (code "17") (name "IO{slash}BOOT") (class "Default")
      (node (ref "BOOT_BUTTON") (pin "3") (pinfunction "3_3") (pintype "passive"))
      (node (ref "BOOT_BUTTON") (pin "4") (pinfunction "4_4") (pintype "passive"))
      (node (ref "C6") (pin "1") (pinfunction "1_1") (pintype "passive"))
      (node (ref "R_BOOT") (pin "1") (pinfunction "1_1") (pintype "passive"))
      (node (ref "U2") (pin "15") (pinfunction "IO9_15") (pintype "bidirectional"))
    )
    (net (code "18") (name "IO{slash}CHANGE") (class "Default")
      (node (ref "C10") (pin "1") (pinfunction "1_1") (pintype "passive"))
      (node (ref "CHANGE_BUTTON") (pin "3") (pinfunction "3_3") (pintype "passive"))
      (node (ref "CHANGE_BUTTON") (pin "4") (pinfunction "4_4") (pintype "passive"))
      (node (ref "R_CHANGE") (pin "1") (pinfunction "1_1") (pintype "passive"))
      (node (ref "U2") (pin "23") (pinfunction "IO15_23") (pintype "bidirectional"))
    )
    (net (code "19") (name "MISO") (class "Default")
      (node (ref "D12") (pin "1") (pinfunction "1_1") (pintype "passive"))
      (node (ref "J4") (pin "P7") (pinfunction "DAT0_P7") (pintype "bidirectional"))
      (node (ref "R8") (pin "1") (pinfunction "1_1") (pintype "passive"))
      (node (ref "TP6") (pin "TP") (pinfunction "TP_TP") (pintype "input"))
      (node (ref "U2") (pin "27") (pinfunction "IO2_27") (pintype "bidirectional"))
      (node (ref "U3") (pin "2") (pinfunction "DO(IO1)_2") (pintype "bidirectional"))
    )
    (net (code "20") (name "MOSI") (class "Default")
      (node (ref "D11") (pin "1") (pinfunction "1_1") (pintype "passive"))
      (node (ref "J1") (pin "14") (pinfunction "14_14") (pintype "bidirectional"))
      (node (ref "J4") (pin "P3") (pinfunction "CMD_P3") (pintype "bidirectional"))
      (node (ref "R7") (pin "1") (pinfunction "1_1") (pintype "passive"))
      (node (ref "TP7") (pin "TP") (pinfunction "TP_TP") (pintype "input"))
      (node (ref "U2") (pin "7") (pinfunction "IO7_7") (pintype "bidirectional"))
      (node (ref "U3") (pin "5") (pinfunction "DI(IO0)_5") (pintype "bidirectional"))
    )
    (net (code "21") (name "Net-(CHG_LED-PadC)") (class "Default")
      (node (ref "CHG_LED") (pin "C") (pinfunction "C_C") (pintype "passive"))
      (node (ref "R1_BAT") (pin "1") (pinfunction "1_1") (pintype "passive"))
    )
    (net (code "22") (name "Net-(D2-CATHODE)") (class "Default")
      (node (ref "C1_BAT1") (pin "1") (pinfunction "1_1") (pintype "passive"))
      (node (ref "D2") (pin "1") (pinfunction "CATHODE_1") (pintype "bidirectional"))
      (node (ref "IC4") (pin "1") (pinfunction "VIN_1") (pintype "bidirectional"))
      (node (ref "IC4") (pin "3") (pinfunction "CE_3") (pintype "bidirectional"))
      (node (ref "Q1") (pin "2") (pinfunction "S_2") (pintype "bidirectional"))
    )
    (net (code "23") (name "Net-(D3-A)") (class "Default")
      (node (ref "C4") (pin "1") (pinfunction "1_1") (pintype "passive"))
      (node (ref "D3") (pin "2") (pinfunction "A_2") (pintype "bidirectional"))
      (node (ref "D4") (pin "1") (pinfunction "K_1") (pintype "bidirectional"))
    )
    (net (code "24") (name "Net-(D7-CATHODE)") (class "Default")
      (node (ref "D7") (pin "1") (pinfunction "CATHODE_1") (pintype "bidirectional"))
      (node (ref "R_CAPACITOR") (pin "2") (pinfunction "2_2") (pintype "passive"))
    )
    (net (code "25") (name "Net-(EPD_C1-Pad2)") (class "Default")
      (node (ref "EPD_C1") (pin "2") (pinfunction "2_2") (pintype "passive"))
      (node (ref "J1") (pin "4") (pinfunction "4_4") (pintype "bidirectional"))
    )
    (net (code "26") (name "Net-(EPD_C2-Pad2)") (class "Default")
      (node (ref "EPD_C2") (pin "2") (pinfunction "2_2") (pintype "passive"))
      (node (ref "J1") (pin "5") (pinfunction "5_5") (pintype "bidirectional"))
    )
    (net (code "27") (name "Net-(EPD_C6-Pad2)") (class "Default")
      (node (ref "EPD_C6") (pin "2") (pinfunction "2_2") (pintype "passive"))
      (node (ref "J1") (pin "18") (pinfunction "18_18") (pintype "bidirectional"))
    )
    (net (code "28") (name "Net-(EPD_C7-Pad2)") (class "Default")
      (node (ref "EPD_C7") (pin "2") (pinfunction "2_2") (pintype "passive"))
      (node (ref "J1") (pin "19") (pinfunction "19_19") (pintype "bidirectional"))
    )
    (net (code "29") (name "Net-(EPD_C8-Pad2)") (class "Default")
      (node (ref "EPD_C8") (pin "2") (pinfunction "2_2") (pintype "passive"))
      (node (ref "J1") (pin "20") (pinfunction "20_20") (pintype "bidirectional"))
    )
    (net (code "30") (name "Net-(EPD_C10-Pad2)") (class "Default")
      (node (ref "EPD_C10") (pin "2") (pinfunction "2_2") (pintype "passive"))
      (node (ref "J1") (pin "22") (pinfunction "22_22") (pintype "bidirectional"))
    )
    (net (code "31") (name "Net-(EPD_C12-Pad2)") (class "Default")
      (node (ref "EPD_C12") (pin "2") (pinfunction "2_2") (pintype "passive"))
      (node (ref "J1") (pin "24") (pinfunction "24_24") (pintype "bidirectional"))
    )
    (net (code "32") (name "Net-(IC1-CT)") (class "Default")
      (node (ref "C_DELAY") (pin "1") (pinfunction "1_1") (pintype "passive"))
      (node (ref "IC1") (pin "5") (pinfunction "CT_5") (pintype "bidirectional"))
    )
    (net (code "33") (name "Net-(J2-PadA5)") (class "Default")
      (node (ref "J2") (pin "A5") (pinfunction "A5_A5") (pintype "bidirectional"))
      (node (ref "R2-USB1") (pin "2") (pinfunction "2_2") (pintype "passive"))
    )
    (net (code "34") (name "Net-(J2-PadB5)") (class "Default")
      (node (ref "J2") (pin "B5") (pinfunction "B5_B5") (pintype "bidirectional"))
      (node (ref "R2-USB") (pin "1") (pinfunction "1_1") (pintype "passive"))
    )
    (net (code "35") (name "Net-(MCP73831-PROG)") (class "Default")
      (node (ref "MCP73831") (pin "5") (pinfunction "PROG_5") (pintype "input"))
      (node (ref "R2_BAT") (pin "2") (pinfunction "2_2") (pintype "passive"))
    )
    (net (code "36") (name "Net-(MCP73831-STAT)") (class "Default")
      (node (ref "MCP73831") (pin "1") (pinfunction "STAT_1") (pintype "output"))
      (node (ref "R1_BAT") (pin "2") (pinfunction "2_2") (pintype "passive"))
    )
    (net (code "37") (name "PREVGH") (class "Default")
      (node (ref "D5") (pin "1") (pinfunction "K_1") (pintype "bidirectional"))
      (node (ref "EPD_C9") (pin "2") (pinfunction "2_2") (pintype "passive"))
      (node (ref "J1") (pin "21") (pinfunction "21_21") (pintype "bidirectional"))
    )
    (net (code "38") (name "PREVGL") (class "Default")
      (node (ref "D4") (pin "2") (pinfunction "A_2") (pintype "bidirectional"))
      (node (ref "EPD_C11") (pin "2") (pinfunction "2_2") (pintype "passive"))
      (node (ref "J1") (pin "23") (pinfunction "23_23") (pintype "bidirectional"))
    )
    (net (code "39") (name "RESE") (class "Default")
      (node (ref "J1") (pin "3") (pinfunction "3_3") (pintype "bidirectional"))
      (node (ref "Q3") (pin "2") (pinfunction "S_2") (pintype "bidirectional"))
      (node (ref "R3") (pin "2") (pinfunction "2_2") (pintype "passive"))
    )
    (net (code "40") (name "RESE'") (class "Default")
      (node (ref "R2") (pin "2") (pinfunction "2_2") (pintype "passive"))
      (node (ref "R3") (pin "1") (pinfunction "1_1") (pintype "passive"))
      (node (ref "SJ1") (pin "2") (pinfunction "2_2") (pintype "passive"))
    )
    (net (code "41") (name "RESET") (class "Default")
      (node (ref "C5") (pin "1") (pinfunction "1_1") (pintype "passive"))
      (node (ref "IC1") (pin "1") (pinfunction "VOUT_1") (pintype "bidirectional"))
      (node (ref "RESET_BUTTON") (pin "3") (pinfunction "3_3") (pintype "passive"))
      (node (ref "RESET_BUTTON") (pin "4") (pinfunction "4_4") (pintype "passive"))
      (node (ref "R_RESET") (pin "1") (pinfunction "1_1") (pintype "passive"))
      (node (ref "U2") (pin "3") (pinfunction "EN_3") (pintype "input"))
    )
    (net (code "42") (name "RTC_RST") (class "Default")
      (node (ref "U1") (pin "4") (pinfunction "~{RST}_4") (pintype "input"))
      (node (ref "U2") (pin "16") (pinfunction "IO18_16") (pintype "bidirectional"))
    )
    (net (code "43") (name "RX") (class "Default")
      (node (ref "TP2") (pin "TP") (pinfunction "TP_TP") (pintype "input"))
      (node (ref "U2") (pin "24") (pinfunction "RXD0/GPIO17_24") (pintype "bidirectional"))
    )
    (net (code "44") (name "SCK") (class "Default")
      (node (ref "D10") (pin "1") (pinfunction "1_1") (pintype "passive"))
      (node (ref "J1") (pin "13") (pinfunction "13_13") (pintype "bidirectional"))
      (node (ref "J4") (pin "P5") (pinfunction "CLK_P5") (pintype "bidirectional"))
      (node (ref "R6") (pin "1") (pinfunction "1_1") (pintype "passive"))
      (node (ref "TP8") (pin "TP") (pinfunction "TP_TP") (pintype "input"))
      (node (ref "U2") (pin "6") (pinfunction "IO6_6") (pintype "bidirectional"))
      (node (ref "U3") (pin "6") (pinfunction "CLK_6") (pintype "input"))
    )
    (net (code "45") (name "SCL") (class "Default")
      (node (ref "J3") (pin "4") (pinfunction "4_4") (pintype "passive"))
      (node (ref "R2_PINH") (pin "1") (pinfunction "1_1") (pintype "passive"))
      (node (ref "SENSOR2") (pin "4") (pinfunction "SCK_4") (pintype "input"))
      (node (ref "U1") (pin "16") (pinfunction "SCL_16") (pintype "input"))
      (node (ref "U2") (pin "20") (pinfunction "IO22_20") (pintype "bidirectional"))
      (node (ref "U4") (pin "7") (pinfunction "SCL_7") (pintype "input"))
    )
    (net (code "46") (name "SDA") (class "Default")
      (node (ref "J3") (pin "3") (pinfunction "3_3") (pintype "passive"))
      (node (ref "R1_PINH") (pin "1") (pinfunction "1_1") (pintype "passive"))
      (node (ref "SENSOR2") (pin "3") (pinfunction "SDI_3") (pintype "bidirectional"))
      (node (ref "U1") (pin "15") (pinfunction "SDA_15") (pintype "bidirectional"))
      (node (ref "U2") (pin "19") (pinfunction "IO21_19") (pintype "bidirectional"))
      (node (ref "U4") (pin "8") (pinfunction "SDA_8") (pintype "bidirectional"))
    )
    (net (code "47") (name "SRC") (class "Default")
      (node (ref "C4") (pin "2") (pinfunction "2_2") (pintype "passive"))
      (node (ref "D5") (pin "2") (pinfunction "A_2") (pintype "bidirectional"))
      (node (ref "L1") (pin "1") (pinfunction "1_1") (pintype "passive"))
      (node (ref "Q3") (pin "3") (pinfunction "D_3") (pintype "bidirectional"))
    )
    (net (code "48") (name "SS_SD") (class "Default")
      (node (ref "D8") (pin "1") (pinfunction "1_1") (pintype "passive"))
      (node (ref "J4") (pin "P2") (pinfunction "CD/DAT3_P2") (pintype "bidirectional"))
      (node (ref "R10") (pin "1") (pinfunction "1_1") (pintype "passive"))
      (node (ref "U2") (pin "4") (pinfunction "IO4_4") (pintype "bidirectional"))
    )
    (net (code "49") (name "TX") (class "Default")
      (node (ref "TP1") (pin "TP") (pinfunction "TP_TP") (pintype "input"))
      (node (ref "U2") (pin "25") (pinfunction "TXD0/GPIO16_25") (pintype "bidirectional"))
    )
    (net (code "50") (name "USB_D+") (class "Default")
      (node (ref "D1") (pin "1") (pinfunction "I/O1_1_1") (pintype "bidirectional"))
      (node (ref "U2") (pin "14") (pinfunction "IO13_14") (pintype "bidirectional"))
    )
    (net (code "51") (name "USB_D-") (class "Default")
      (node (ref "D1") (pin "3") (pinfunction "I/O2_1_3") (pintype "bidirectional"))
      (node (ref "U2") (pin "13") (pinfunction "IO12_13") (pintype "bidirectional"))
    )
    (net (code "52") (name "VBAT") (class "Default")
      (node (ref "C2_BAT") (pin "1") (pinfunction "1_1") (pintype "passive"))
      (node (ref "MCP73831") (pin "3") (pinfunction "VBAT_3") (pintype "power_in"))
      (node (ref "Q1") (pin "3") (pinfunction "D_3") (pintype "bidirectional"))
      (node (ref "TP3") (pin "TP") (pinfunction "TP_TP") (pintype "input"))
      (node (ref "U4") (pin "2") (pinfunction "CELL_2") (pintype "power_in"))
      (node (ref "U4") (pin "3") (pinfunction "VDD_3") (pintype "power_in"))
    )
    (net (code "53") (name "VBUS") (class "Default")
      (node (ref "C1_BAT") (pin "1") (pinfunction "1_1") (pintype "passive"))
      (node (ref "C4_USB") (pin "1") (pinfunction "1_1") (pintype "passive"))
      (node (ref "C5_USB") (pin "1") (pinfunction "1_1") (pintype "passive"))
      (node (ref "CHG_LED") (pin "A") (pinfunction "A_A") (pintype "passive"))
      (node (ref "D1") (pin "5") (pinfunction "VBUS_5") (pintype "bidirectional"))
      (node (ref "D2") (pin "2") (pinfunction "ANODE_2") (pintype "bidirectional"))
      (node (ref "MCP73831") (pin "4") (pinfunction "VIN_4") (pintype "power_in"))
      (node (ref "PFMF.050.1") (pin "2") (pinfunction "2_2") (pintype "passive"))
      (node (ref "Q1") (pin "1") (pinfunction "G_1") (pintype "bidirectional"))
      (node (ref "R1_PWRUSB") (pin "2") (pinfunction "2_2") (pintype "passive"))
      (node (ref "TP14") (pin "TP") (pinfunction "TP_TP") (pintype "input"))
    )
    (net (code "54") (name "VRTC") (class "Default")
      (node (ref "C10_SUPERCAP") (pin "2") (pinfunction "2_2") (pintype "passive"))
      (node (ref "C8") (pin "2") (pinfunction "2_2") (pintype "passive"))
      (node (ref "R_CAPACITOR") (pin "1") (pinfunction "1_1") (pintype "passive"))
      (node (ref "U1") (pin "14") (pinfunction "VBAT_14") (pintype "power_in"))
    )
    (net (code "55") (name "VUSB") (class "Default")
      (node (ref "J2") (pin "A4") (pinfunction "A4_A4") (pintype "bidirectional"))
      (node (ref "J2") (pin "A9") (pinfunction "A9_A9") (pintype "bidirectional"))
      (node (ref "J2") (pin "B4") (pinfunction "B4_B4") (pintype "bidirectional"))
      (node (ref "J2") (pin "B9") (pinfunction "B9_B9") (pintype "bidirectional"))
      (node (ref "PFMF.050.1") (pin "1") (pinfunction "1_1") (pintype "passive"))
    )
    (net (code "56") (name "unconnected-(IC1-NC-Pad4)") (class "Default")
      (node (ref "IC1") (pin "4") (pinfunction "NC_4") (pintype "no_connect"))
    )
    (net (code "57") (name "unconnected-(IC4-NC-Pad4)") (class "Default")
      (node (ref "IC4") (pin "4") (pinfunction "NC_4") (pintype "no_connect"))
    )
    (net (code "58") (name "unconnected-(J1-Pad1)") (class "Default")
      (node (ref "J1") (pin "1") (pinfunction "1_1") (pintype "bidirectional"))
    )
    (net (code "59") (name "unconnected-(J1-Pad6)") (class "Default")
      (node (ref "J1") (pin "6") (pinfunction "6_6") (pintype "bidirectional"))
    )
    (net (code "60") (name "unconnected-(J1-Pad7)") (class "Default")
      (node (ref "J1") (pin "7") (pinfunction "7_7") (pintype "bidirectional"))
    )
    (net (code "61") (name "unconnected-(J2-PadA8)") (class "Default")
      (node (ref "J2") (pin "A8") (pinfunction "A8_A8") (pintype "bidirectional"))
    )
    (net (code "62") (name "unconnected-(J2-PadB8)") (class "Default")
      (node (ref "J2") (pin "B8") (pinfunction "B8_B8") (pintype "bidirectional"))
    )
    (net (code "63") (name "unconnected-(J4-DAT1-PadP8)") (class "Default")
      (node (ref "J4") (pin "P8") (pinfunction "DAT1_P8") (pintype "bidirectional"))
    )
    (net (code "64") (name "unconnected-(J4-DAT2-PadP1)") (class "Default")
      (node (ref "J4") (pin "P1") (pinfunction "DAT2_P1") (pintype "bidirectional"))
    )
    (net (code "65") (name "unconnected-(J4-DETECTION_1-PadS1)") (class "Default")
      (node (ref "J4") (pin "S1") (pinfunction "DETECTION_1_S1") (pintype "bidirectional"))
    )
    (net (code "66") (name "unconnected-(J4-DETECTION_2-PadS2)") (class "Default")
      (node (ref "J4") (pin "S2") (pinfunction "DETECTION_2_S2") (pintype "bidirectional"))
    )
    (net (code "67") (name "unconnected-(U2-NC-Pad22)") (class "Default")
      (node (ref "U2") (pin "22") (pinfunction "NC_22") (pintype "no_connect"))
    )
    (net (code "68") (name "unconnected-(U4-~{ALERT}-Pad5)") (class "Default")
      (node (ref "U4") (pin "5") (pinfunction "~{ALERT}_5") (pintype "output"))
    )
  )
)
